# STC12_CH340E.net
KiCad netlist of a schematic drawn in Altium Designer
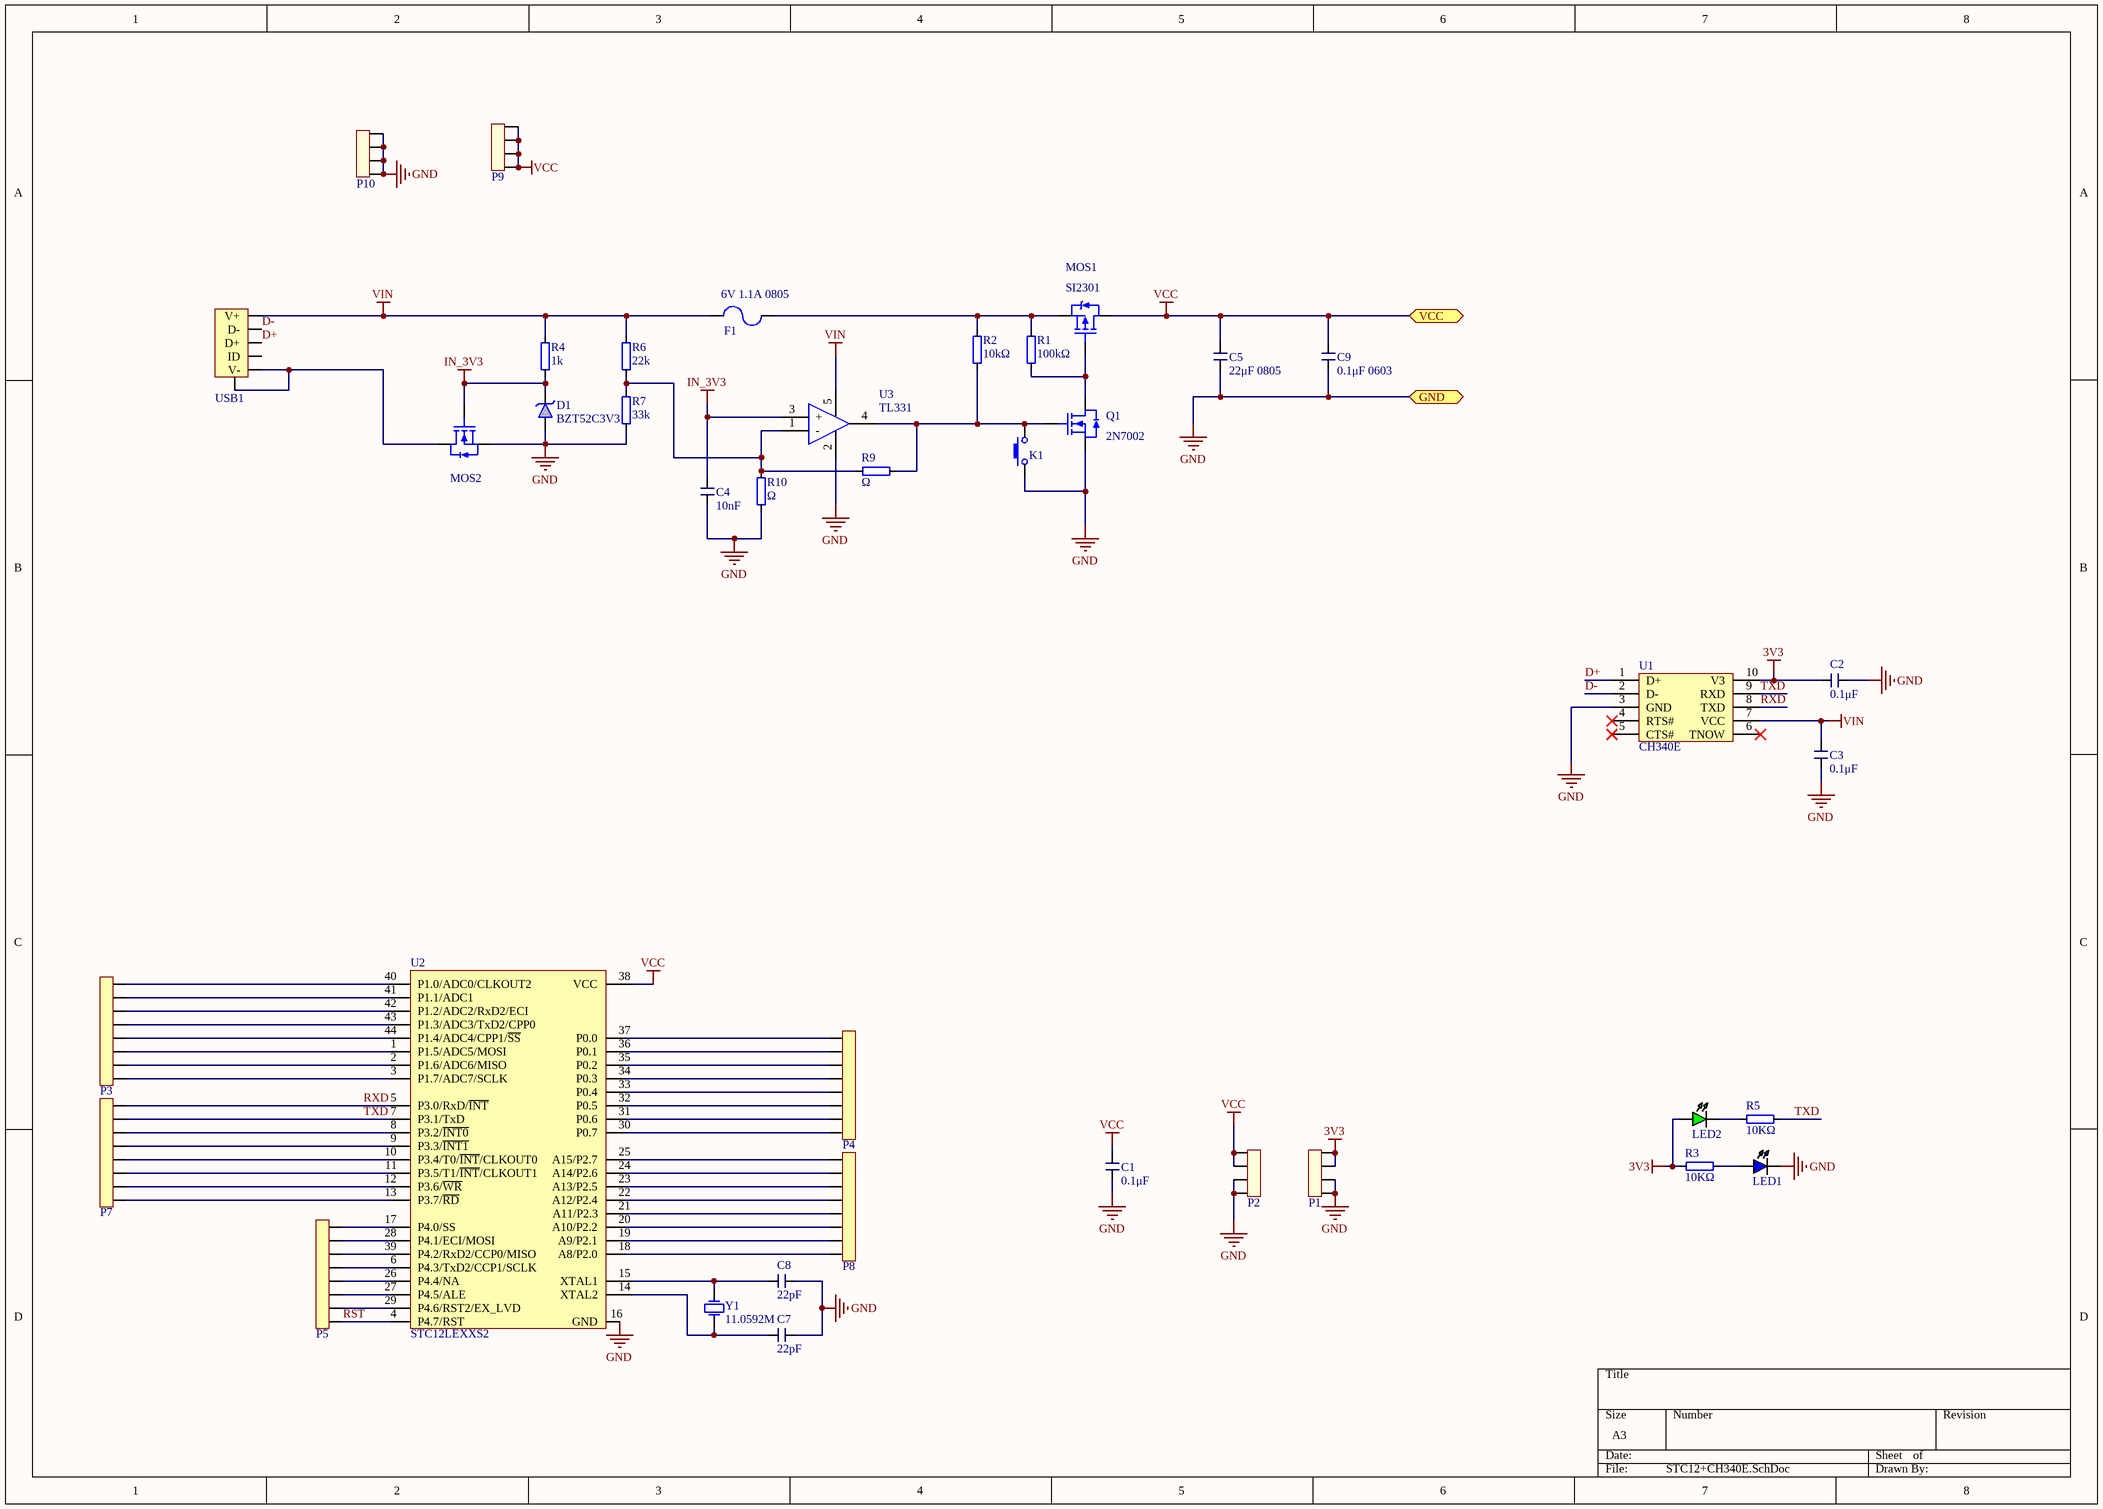
[diagram p0: STC12+CH340E.SchDoc]

(export (version "E")
  (design (tool "Eeschema 10.0.6"))
  (components
    (comp (ref "C1") (value "0.1μF") (footprint "C_0603") (libsource (lib "节能库") (part "C_0603")))
    (comp (ref "C2") (value "0.1μF") (footprint "C_0603") (libsource (lib "节能库") (part "C_0603")))
    (comp (ref "C3") (value "0.1μF") (footprint "C_0603") (libsource (lib "节能库") (part "C_0603")))
    (comp (ref "C4") (value "10nF") (footprint "C_0603") (libsource (lib "节能库") (part "C_0603")))
    (comp (ref "C5") (value "22μF 0805") (footprint "C_0805") (libsource (lib "节能库") (part "C_0805")))
    (comp (ref "C7") (value "22pF") (footprint "C_0603") (libsource (lib "节能库") (part "C_0603")))
    (comp (ref "C8") (value "22pF") (footprint "C_0603") (libsource (lib "节能库") (part "C_0603")))
    (comp (ref "C9") (value "0.1μF 0603") (footprint "C_0603") (libsource (lib "节能库") (part "C_0603")))
    (comp (ref "D1") (value "BZT52C3V3") (footprint "SOD_123") (libsource (lib "节能库") (part "BZT52CxVx")))
    (comp (ref "F1") (value "6V 1.1A 0805") (footprint "FB_0805") (libsource (lib "节能库") (part "FUSE_0805")))
    (comp (ref "K1")
      (value "TACT SWITCH_2_SMD")
      (footprint "TACT SWITCH_2_SMD")
      (libsource (lib "节能库") (part "TACT SWITCH_2_SMD"))
    )
    (comp (ref "LED1")
      (value "LED_0603-B")
      (footprint "LED_0603-B")
      (libsource (lib "节能库") (part "LED_0603-B"))
    )
    (comp (ref "LED2")
      (value "LED_0603-G")
      (footprint "LED_0603-G")
      (libsource (lib "节能库") (part "LED_0603-G"))
    )
    (comp (ref "MOS1") (value "SI2301") (footprint "SOT_23_3") (libsource (lib "节能库") (part "SI2301")))
    (comp (ref "MOS2") (value "AO3400A") (footprint "SOT_23_3") (libsource (lib "节能库") (part "AO3400A")))
    (comp (ref "P1") (value "PIN4") (footprint "PIN_4") (libsource (lib "节能库") (part "PIN4")))
    (comp (ref "P2") (value "PIN4") (footprint "PIN_4") (libsource (lib "") (part "PIN4_2")))
    (comp (ref "P3") (value "PIN8") (footprint "PIN_8") (libsource (lib "") (part "PIN8_1")))
    (comp (ref "P4") (value "PIN8") (footprint "PIN_8") (libsource (lib "节能库") (part "PIN8")))
    (comp (ref "P5") (value "PIN8") (footprint "PIN_8") (libsource (lib "") (part "PIN8_1")))
    (comp (ref "P7") (value "PIN8") (footprint "PIN_8") (libsource (lib "") (part "PIN8_1")))
    (comp (ref "P8") (value "PIN8") (footprint "PIN_8") (libsource (lib "节能库") (part "PIN8")))
    (comp (ref "P9") (value "PIN4") (footprint "PIN_4") (libsource (lib "") (part "PIN4_1")))
    (comp (ref "P10") (value "PIN4") (footprint "PIN_4") (libsource (lib "") (part "PIN4_1")))
    (comp (ref "Q1") (value "2N7002") (footprint "SOT_23_3") (libsource (lib "节能库") (part "2N7002")))
    (comp (ref "R1") (value "100kΩ") (footprint "R_0603") (libsource (lib "节能库") (part "R_0603")))
    (comp (ref "R2") (value "10kΩ") (footprint "R_0603") (libsource (lib "节能库") (part "R_0603")))
    (comp (ref "R3") (value "10KΩ") (footprint "R_0603") (libsource (lib "节能库") (part "R_0603")))
    (comp (ref "R4") (value "1k") (footprint "R_0603") (libsource (lib "节能库") (part "R_0603")))
    (comp (ref "R5") (value "10KΩ") (footprint "R_0603") (libsource (lib "节能库") (part "R_0603")))
    (comp (ref "R6") (value "22k") (footprint "R_0603") (libsource (lib "节能库") (part "R_0603")))
    (comp (ref "R7") (value "33k") (footprint "R_0603") (libsource (lib "节能库") (part "R_0603")))
    (comp (ref "R9") (value "Ω") (footprint "R_0603") (libsource (lib "节能库") (part "R_0603")))
    (comp (ref "R10") (value "Ω") (footprint "R_0603") (libsource (lib "节能库") (part "R_0603")))
    (comp (ref "U1") (value "CH340E") (footprint "MSOP_10") (libsource (lib "节能库") (part "CH340E")))
    (comp (ref "U2")
      (value "STC12LEXXS2")
      (footprint "LQFP_44")
      (libsource (lib "节能库") (part "STC12LE5AXXS2 - LQPF44"))
    )
    (comp (ref "U3") (value "TL331") (footprint "SOT_23_5") (libsource (lib "节能库") (part "TL331")))
    (comp (ref "USB1")
      (value "MICRO USB B")
      (footprint "MICRO USB B")
      (libsource (lib "节能库") (part "MICRO USB B"))
    )
    (comp (ref "Y1")
      (value "11.0592M")
      (footprint "Crystal_HC_49US")
      (libsource (lib "节能库") (part "Crystal_HC_49US"))
    )
  )
  (nets
    (net (code "1") (name "/D+") (class "Default")
      (node (ref "U1") (pin "1") (pinfunction "D+_1") (pintype "passive"))
      (node (ref "USB1") (pin "3") (pinfunction "D+_3") (pintype "passive"))
    )
    (net (code "2") (name "/D-") (class "Default")
      (node (ref "U1") (pin "2") (pinfunction "D-_2") (pintype "passive"))
      (node (ref "USB1") (pin "2") (pinfunction "D-_2") (pintype "passive"))
    )
    (net (code "3") (name "/RST") (class "Default")
      (node (ref "P5") (pin "8") (pinfunction "8_8") (pintype "passive"))
      (node (ref "U2") (pin "4") (pinfunction "P4.7/RST_4") (pintype "passive"))
    )
    (net (code "4") (name "/RXD") (class "Default")
      (node (ref "P7") (pin "1") (pinfunction "1_1") (pintype "passive"))
      (node (ref "U1") (pin "8") (pinfunction "TXD_8") (pintype "passive"))
      (node (ref "U2") (pin "5") (pinfunction "P3.0/RxD/~{INT}_5") (pintype "passive"))
    )
    (net (code "5") (name "/TXD") (class "Default")
      (node (ref "P7") (pin "2") (pinfunction "2_2") (pintype "passive"))
      (node (ref "R5") (pin "2") (pintype "passive"))
      (node (ref "U1") (pin "9") (pinfunction "RXD_9") (pintype "passive"))
      (node (ref "U2") (pin "7") (pinfunction "P3.1/TxD_7") (pintype "passive"))
    )
    (net (code "6") (name "3V3") (class "Default")
      (node (ref "C2") (pin "2") (pinfunction "2_2") (pintype "passive"))
      (node (ref "LED2") (pin "1") (pinfunction "1_1") (pintype "passive"))
      (node (ref "P1") (pin "3") (pinfunction "3_3") (pintype "passive"))
      (node (ref "P1") (pin "4") (pinfunction "4_4") (pintype "passive"))
      (node (ref "R3") (pin "1") (pintype "passive"))
      (node (ref "U1") (pin "10") (pinfunction "V3_10") (pintype "passive"))
    )
    (net (code "7") (name "GND") (class "Default")
      (node (ref "C1") (pin "2") (pinfunction "2_2") (pintype "passive"))
      (node (ref "C2") (pin "1") (pinfunction "1_1") (pintype "passive"))
      (node (ref "C3") (pin "1") (pinfunction "1_1") (pintype "passive"))
      (node (ref "C4") (pin "2") (pinfunction "2_2") (pintype "passive"))
      (node (ref "C5") (pin "2") (pinfunction "2_2") (pintype "passive"))
      (node (ref "C7") (pin "2") (pinfunction "2_2") (pintype "passive"))
      (node (ref "C8") (pin "2") (pinfunction "2_2") (pintype "passive"))
      (node (ref "C9") (pin "2") (pinfunction "2_2") (pintype "passive"))
      (node (ref "D1") (pin "1") (pinfunction "A_1") (pintype "passive"))
      (node (ref "K1") (pin "1") (pinfunction "1_1") (pintype "passive"))
      (node (ref "LED1") (pin "2") (pinfunction "2_2") (pintype "passive"))
      (node (ref "MOS2") (pin "2") (pinfunction "S_2") (pintype "passive"))
      (node (ref "P1") (pin "1") (pinfunction "1_1") (pintype "passive"))
      (node (ref "P1") (pin "2") (pinfunction "2_2") (pintype "passive"))
      (node (ref "P10") (pin "1") (pinfunction "1_1") (pintype "passive"))
      (node (ref "P10") (pin "2") (pinfunction "2_2") (pintype "passive"))
      (node (ref "P10") (pin "3") (pinfunction "3_3") (pintype "passive"))
      (node (ref "P10") (pin "4") (pinfunction "4_4") (pintype "passive"))
      (node (ref "P2") (pin "1") (pinfunction "1_1") (pintype "passive"))
      (node (ref "P2") (pin "2") (pinfunction "2_2") (pintype "passive"))
      (node (ref "Q1") (pin "2") (pinfunction "S_2") (pintype "passive"))
      (node (ref "R10") (pin "1") (pintype "passive"))
      (node (ref "R7") (pin "1") (pintype "passive"))
      (node (ref "U1") (pin "3") (pinfunction "GND_3") (pintype "passive"))
      (node (ref "U2") (pin "16") (pinfunction "GND_16") (pintype "passive"))
      (node (ref "U3") (pin "2") (pinfunction "GND_2") (pintype "passive"))
    )
    (net (code "8") (name "IN_3V3") (class "Default")
      (node (ref "C4") (pin "1") (pinfunction "1_1") (pintype "passive"))
      (node (ref "D1") (pin "2") (pinfunction "K_2") (pintype "passive"))
      (node (ref "MOS2") (pin "1") (pinfunction "G_1") (pintype "passive"))
      (node (ref "R4") (pin "1") (pintype "passive"))
      (node (ref "U3") (pin "3") (pinfunction "+_3") (pintype "passive"))
    )
    (net (code "9") (name "Net-(LED1-Pad1)") (class "Default")
      (node (ref "LED1") (pin "1") (pinfunction "1_1") (pintype "passive"))
      (node (ref "R3") (pin "2") (pintype "passive"))
    )
    (net (code "10") (name "Net-(LED2-Pad2)") (class "Default")
      (node (ref "LED2") (pin "2") (pinfunction "2_2") (pintype "passive"))
      (node (ref "R5") (pin "1") (pintype "passive"))
    )
    (net (code "11") (name "Net-(MOS1-G)") (class "Default")
      (node (ref "MOS1") (pin "1") (pinfunction "G_1") (pintype "passive"))
      (node (ref "Q1") (pin "3") (pinfunction "D_3") (pintype "passive"))
      (node (ref "R1") (pin "1") (pintype "passive"))
    )
    (net (code "12") (name "Net-(MOS1-S)") (class "Default")
      (node (ref "F1") (pin "2") (pinfunction "2_2") (pintype "passive"))
      (node (ref "MOS1") (pin "2") (pinfunction "S_2") (pintype "passive"))
      (node (ref "R1") (pin "2") (pintype "passive"))
      (node (ref "R2") (pin "2") (pintype "passive"))
    )
    (net (code "13") (name "Net-(MOS2-D)") (class "Default")
      (node (ref "MOS2") (pin "3") (pinfunction "D_3") (pintype "passive"))
      (node (ref "USB1") (pin "0") (pinfunction "GND_0") (pintype "passive"))
      (node (ref "USB1") (pin "5") (pinfunction "V-_5") (pintype "passive"))
    )
    (net (code "14") (name "Net-(Q1-G)") (class "Default")
      (node (ref "K1") (pin "2") (pinfunction "2_2") (pintype "passive"))
      (node (ref "Q1") (pin "1") (pinfunction "G_1") (pintype "passive"))
      (node (ref "R2") (pin "1") (pintype "passive"))
      (node (ref "R9") (pin "2") (pintype "passive"))
      (node (ref "U3") (pin "4") (pinfunction "OUT_4") (pintype "passive"))
    )
    (net (code "15") (name "Net-(U2-A8{slash}P2.0)") (class "Default")
      (node (ref "P8") (pin "1") (pinfunction "1_1") (pintype "passive"))
      (node (ref "U2") (pin "18") (pinfunction "A8/P2.0_18") (pintype "passive"))
    )
    (net (code "16") (name "Net-(U2-A9{slash}P2.1)") (class "Default")
      (node (ref "P8") (pin "2") (pinfunction "2_2") (pintype "passive"))
      (node (ref "U2") (pin "19") (pinfunction "A9/P2.1_19") (pintype "passive"))
    )
    (net (code "17") (name "Net-(U2-A10{slash}P2.2)") (class "Default")
      (node (ref "P8") (pin "3") (pinfunction "3_3") (pintype "passive"))
      (node (ref "U2") (pin "20") (pinfunction "A10/P2.2_20") (pintype "passive"))
    )
    (net (code "18") (name "Net-(U2-A11{slash}P2.3)") (class "Default")
      (node (ref "P8") (pin "4") (pinfunction "4_4") (pintype "passive"))
      (node (ref "U2") (pin "21") (pinfunction "A11/P2.3_21") (pintype "passive"))
    )
    (net (code "19") (name "Net-(U2-A12{slash}P2.4)") (class "Default")
      (node (ref "P8") (pin "5") (pinfunction "5_5") (pintype "passive"))
      (node (ref "U2") (pin "22") (pinfunction "A12/P2.4_22") (pintype "passive"))
    )
    (net (code "20") (name "Net-(U2-A13{slash}P2.5)") (class "Default")
      (node (ref "P8") (pin "6") (pinfunction "6_6") (pintype "passive"))
      (node (ref "U2") (pin "23") (pinfunction "A13/P2.5_23") (pintype "passive"))
    )
    (net (code "21") (name "Net-(U2-A14{slash}P2.6)") (class "Default")
      (node (ref "P8") (pin "7") (pinfunction "7_7") (pintype "passive"))
      (node (ref "U2") (pin "24") (pinfunction "A14/P2.6_24") (pintype "passive"))
    )
    (net (code "22") (name "Net-(U2-A15{slash}P2.7)") (class "Default")
      (node (ref "P8") (pin "8") (pinfunction "8_8") (pintype "passive"))
      (node (ref "U2") (pin "25") (pinfunction "A15/P2.7_25") (pintype "passive"))
    )
    (net (code "23") (name "Net-(U2-P0.0)") (class "Default")
      (node (ref "P4") (pin "8") (pinfunction "8_8") (pintype "passive"))
      (node (ref "U2") (pin "37") (pinfunction "P0.0_37") (pintype "passive"))
    )
    (net (code "24") (name "Net-(U2-P0.1)") (class "Default")
      (node (ref "P4") (pin "7") (pinfunction "7_7") (pintype "passive"))
      (node (ref "U2") (pin "36") (pinfunction "P0.1_36") (pintype "passive"))
    )
    (net (code "25") (name "Net-(U2-P0.2)") (class "Default")
      (node (ref "P4") (pin "6") (pinfunction "6_6") (pintype "passive"))
      (node (ref "U2") (pin "35") (pinfunction "P0.2_35") (pintype "passive"))
    )
    (net (code "26") (name "Net-(U2-P0.3)") (class "Default")
      (node (ref "P4") (pin "5") (pinfunction "5_5") (pintype "passive"))
      (node (ref "U2") (pin "34") (pinfunction "P0.3_34") (pintype "passive"))
    )
    (net (code "27") (name "Net-(U2-P0.4)") (class "Default")
      (node (ref "P4") (pin "4") (pinfunction "4_4") (pintype "passive"))
      (node (ref "U2") (pin "33") (pinfunction "P0.4_33") (pintype "passive"))
    )
    (net (code "28") (name "Net-(U2-P0.5)") (class "Default")
      (node (ref "P4") (pin "3") (pinfunction "3_3") (pintype "passive"))
      (node (ref "U2") (pin "32") (pinfunction "P0.5_32") (pintype "passive"))
    )
    (net (code "29") (name "Net-(U2-P0.6)") (class "Default")
      (node (ref "P4") (pin "2") (pinfunction "2_2") (pintype "passive"))
      (node (ref "U2") (pin "31") (pinfunction "P0.6_31") (pintype "passive"))
    )
    (net (code "30") (name "Net-(U2-P0.7)") (class "Default")
      (node (ref "P4") (pin "1") (pinfunction "1_1") (pintype "passive"))
      (node (ref "U2") (pin "30") (pinfunction "P0.7_30") (pintype "passive"))
    )
    (net (code "31") (name "Net-(U2-P1.0{slash}ADC0{slash}CLKOUT2)") (class "Default")
      (node (ref "P3") (pin "1") (pinfunction "1_1") (pintype "passive"))
      (node (ref "U2") (pin "40") (pinfunction "P1.0/ADC0/CLKOUT2_40") (pintype "passive"))
    )
    (net (code "32") (name "Net-(U2-P1.1{slash}ADC1)") (class "Default")
      (node (ref "P3") (pin "2") (pinfunction "2_2") (pintype "passive"))
      (node (ref "U2") (pin "41") (pinfunction "P1.1/ADC1_41") (pintype "passive"))
    )
    (net (code "33") (name "Net-(U2-P1.2{slash}ADC2{slash}RxD2{slash}ECI)") (class "Default")
      (node (ref "P3") (pin "3") (pinfunction "3_3") (pintype "passive"))
      (node (ref "U2") (pin "42") (pinfunction "P1.2/ADC2/RxD2/ECI_42") (pintype "passive"))
    )
    (net (code "34") (name "Net-(U2-P1.3{slash}ADC3{slash}TxD2{slash}CPP0)") (class "Default")
      (node (ref "P3") (pin "4") (pinfunction "4_4") (pintype "passive"))
      (node (ref "U2") (pin "43") (pinfunction "P1.3/ADC3/TxD2/CPP0_43") (pintype "passive"))
    )
    (net (code "35") (name "Net-(U2-P1.4{slash}ADC4{slash}CPP1{slash}~{SS})") (class "Default")
      (node (ref "P3") (pin "5") (pinfunction "5_5") (pintype "passive"))
      (node (ref "U2") (pin "44") (pinfunction "P1.4/ADC4/CPP1/~{SS}_44") (pintype "passive"))
    )
    (net (code "36") (name "Net-(U2-P1.5{slash}ADC5{slash}MOSI)") (class "Default")
      (node (ref "P3") (pin "6") (pinfunction "6_6") (pintype "passive"))
      (node (ref "U2") (pin "1") (pinfunction "P1.5/ADC5/MOSI_1") (pintype "passive"))
    )
    (net (code "37") (name "Net-(U2-P1.6{slash}ADC6{slash}MISO)") (class "Default")
      (node (ref "P3") (pin "7") (pinfunction "7_7") (pintype "passive"))
      (node (ref "U2") (pin "2") (pinfunction "P1.6/ADC6/MISO_2") (pintype "passive"))
    )
    (net (code "38") (name "Net-(U2-P1.7{slash}ADC7{slash}SCLK)") (class "Default")
      (node (ref "P3") (pin "8") (pinfunction "8_8") (pintype "passive"))
      (node (ref "U2") (pin "3") (pinfunction "P1.7/ADC7/SCLK_3") (pintype "passive"))
    )
    (net (code "39") (name "Net-(U2-P3.2{slash}~{INT0})") (class "Default")
      (node (ref "P7") (pin "3") (pinfunction "3_3") (pintype "passive"))
      (node (ref "U2") (pin "8") (pinfunction "P3.2/~{INT0}_8") (pintype "passive"))
    )
    (net (code "40") (name "Net-(U2-P3.3{slash}~{INT1})") (class "Default")
      (node (ref "P7") (pin "4") (pinfunction "4_4") (pintype "passive"))
      (node (ref "U2") (pin "9") (pinfunction "P3.3/~{INT1}_9") (pintype "passive"))
    )
    (net (code "41") (name "Net-(U2-P3.4{slash}T0{slash}~{INT}{slash}CLKOUT0)") (class "Default")
      (node (ref "P7") (pin "5") (pinfunction "5_5") (pintype "passive"))
      (node (ref "U2") (pin "10") (pinfunction "P3.4/T0/~{INT}/CLKOUT0_10") (pintype "passive"))
    )
    (net (code "42") (name "Net-(U2-P3.5{slash}T1{slash}~{INT}{slash}CLKOUT1)") (class "Default")
      (node (ref "P7") (pin "6") (pinfunction "6_6") (pintype "passive"))
      (node (ref "U2") (pin "11") (pinfunction "P3.5/T1/~{INT}/CLKOUT1_11") (pintype "passive"))
    )
    (net (code "43") (name "Net-(U2-P3.6{slash}~{WR})") (class "Default")
      (node (ref "P7") (pin "7") (pinfunction "7_7") (pintype "passive"))
      (node (ref "U2") (pin "12") (pinfunction "P3.6/~{WR}_12") (pintype "passive"))
    )
    (net (code "44") (name "Net-(U2-P3.7{slash}~{RD})") (class "Default")
      (node (ref "P7") (pin "8") (pinfunction "8_8") (pintype "passive"))
      (node (ref "U2") (pin "13") (pinfunction "P3.7/~{RD}_13") (pintype "passive"))
    )
    (net (code "45") (name "Net-(U2-P4.0{slash}SS)") (class "Default")
      (node (ref "P5") (pin "1") (pinfunction "1_1") (pintype "passive"))
      (node (ref "U2") (pin "17") (pinfunction "P4.0/SS_17") (pintype "passive"))
    )
    (net (code "46") (name "Net-(U2-P4.1{slash}ECI{slash}MOSI)") (class "Default")
      (node (ref "P5") (pin "2") (pinfunction "2_2") (pintype "passive"))
      (node (ref "U2") (pin "28") (pinfunction "P4.1/ECI/MOSI_28") (pintype "passive"))
    )
    (net (code "47") (name "Net-(U2-P4.2{slash}RxD2{slash}CCP0{slash}MISO)") (class "Default")
      (node (ref "P5") (pin "3") (pinfunction "3_3") (pintype "passive"))
      (node (ref "U2") (pin "39") (pinfunction "P4.2/RxD2/CCP0/MISO_39") (pintype "passive"))
    )
    (net (code "48") (name "Net-(U2-P4.3{slash}TxD2{slash}CCP1{slash}SCLK)") (class "Default")
      (node (ref "P5") (pin "4") (pinfunction "4_4") (pintype "passive"))
      (node (ref "U2") (pin "6") (pinfunction "P4.3/TxD2/CCP1/SCLK_6") (pintype "passive"))
    )
    (net (code "49") (name "Net-(U2-P4.4{slash}NA)") (class "Default")
      (node (ref "P5") (pin "5") (pinfunction "5_5") (pintype "passive"))
      (node (ref "U2") (pin "26") (pinfunction "P4.4/NA_26") (pintype "passive"))
    )
    (net (code "50") (name "Net-(U2-P4.5{slash}ALE)") (class "Default")
      (node (ref "P5") (pin "6") (pinfunction "6_6") (pintype "passive"))
      (node (ref "U2") (pin "27") (pinfunction "P4.5/ALE_27") (pintype "passive"))
    )
    (net (code "51") (name "Net-(U2-P4.6{slash}RST2{slash}EX_LVD)") (class "Default")
      (node (ref "P5") (pin "7") (pinfunction "7_7") (pintype "passive"))
      (node (ref "U2") (pin "29") (pinfunction "P4.6/RST2/EX_LVD_29") (pintype "passive"))
    )
    (net (code "52") (name "Net-(U2-XTAL1)") (class "Default")
      (node (ref "C8") (pin "1") (pinfunction "1_1") (pintype "passive"))
      (node (ref "U2") (pin "15") (pinfunction "XTAL1_15") (pintype "passive"))
      (node (ref "Y1") (pin "2") (pinfunction "OSC2_2") (pintype "passive"))
    )
    (net (code "53") (name "Net-(U2-XTAL2)") (class "Default")
      (node (ref "C7") (pin "1") (pinfunction "1_1") (pintype "passive"))
      (node (ref "U2") (pin "14") (pinfunction "XTAL2_14") (pintype "passive"))
      (node (ref "Y1") (pin "1") (pinfunction "OSC1_1") (pintype "passive"))
    )
    (net (code "54") (name "Net-(U3--)") (class "Default")
      (node (ref "R10") (pin "2") (pintype "passive"))
      (node (ref "R6") (pin "1") (pintype "passive"))
      (node (ref "R7") (pin "2") (pintype "passive"))
      (node (ref "R9") (pin "1") (pintype "passive"))
      (node (ref "U3") (pin "1") (pinfunction "-_1") (pintype "passive"))
    )
    (net (code "55") (name "VCC") (class "Default")
      (node (ref "C1") (pin "1") (pinfunction "1_1") (pintype "passive"))
      (node (ref "C5") (pin "1") (pinfunction "1_1") (pintype "passive"))
      (node (ref "C9") (pin "1") (pinfunction "1_1") (pintype "passive"))
      (node (ref "MOS1") (pin "3") (pinfunction "D_3") (pintype "passive"))
      (node (ref "P2") (pin "3") (pinfunction "3_3") (pintype "passive"))
      (node (ref "P2") (pin "4") (pinfunction "4_4") (pintype "passive"))
      (node (ref "P9") (pin "1") (pinfunction "1_1") (pintype "passive"))
      (node (ref "P9") (pin "2") (pinfunction "2_2") (pintype "passive"))
      (node (ref "P9") (pin "3") (pinfunction "3_3") (pintype "passive"))
      (node (ref "P9") (pin "4") (pinfunction "4_4") (pintype "passive"))
      (node (ref "U2") (pin "38") (pinfunction "VCC_38") (pintype "passive"))
    )
    (net (code "56") (name "VIN") (class "Default")
      (node (ref "C3") (pin "2") (pinfunction "2_2") (pintype "passive"))
      (node (ref "F1") (pin "1") (pinfunction "1_1") (pintype "passive"))
      (node (ref "R4") (pin "2") (pintype "passive"))
      (node (ref "R6") (pin "2") (pintype "passive"))
      (node (ref "U1") (pin "7") (pinfunction "VCC_7") (pintype "passive"))
      (node (ref "U3") (pin "5") (pinfunction "VCC_5") (pintype "passive"))
      (node (ref "USB1") (pin "1") (pinfunction "V+_1") (pintype "passive"))
    )
    (net (code "57") (name "unconnected-(U1-CTS#-Pad5)") (class "Default")
      (node (ref "U1") (pin "5") (pinfunction "CTS#_5") (pintype "passive+no_connect"))
    )
    (net (code "58") (name "unconnected-(U1-RTS#-Pad4)") (class "Default")
      (node (ref "U1") (pin "4") (pinfunction "RTS#_4") (pintype "passive+no_connect"))
    )
    (net (code "59") (name "unconnected-(U1-TNOW-Pad6)") (class "Default")
      (node (ref "U1") (pin "6") (pinfunction "TNOW_6") (pintype "passive+no_connect"))
    )
    (net (code "60") (name "unconnected-(USB1-ID-Pad4)") (class "Default")
      (node (ref "USB1") (pin "4") (pinfunction "ID_4") (pintype "passive"))
    )
  )
)
